# custom_numpad.net
KiCad netlist of a schematic drawn in EasyEDA
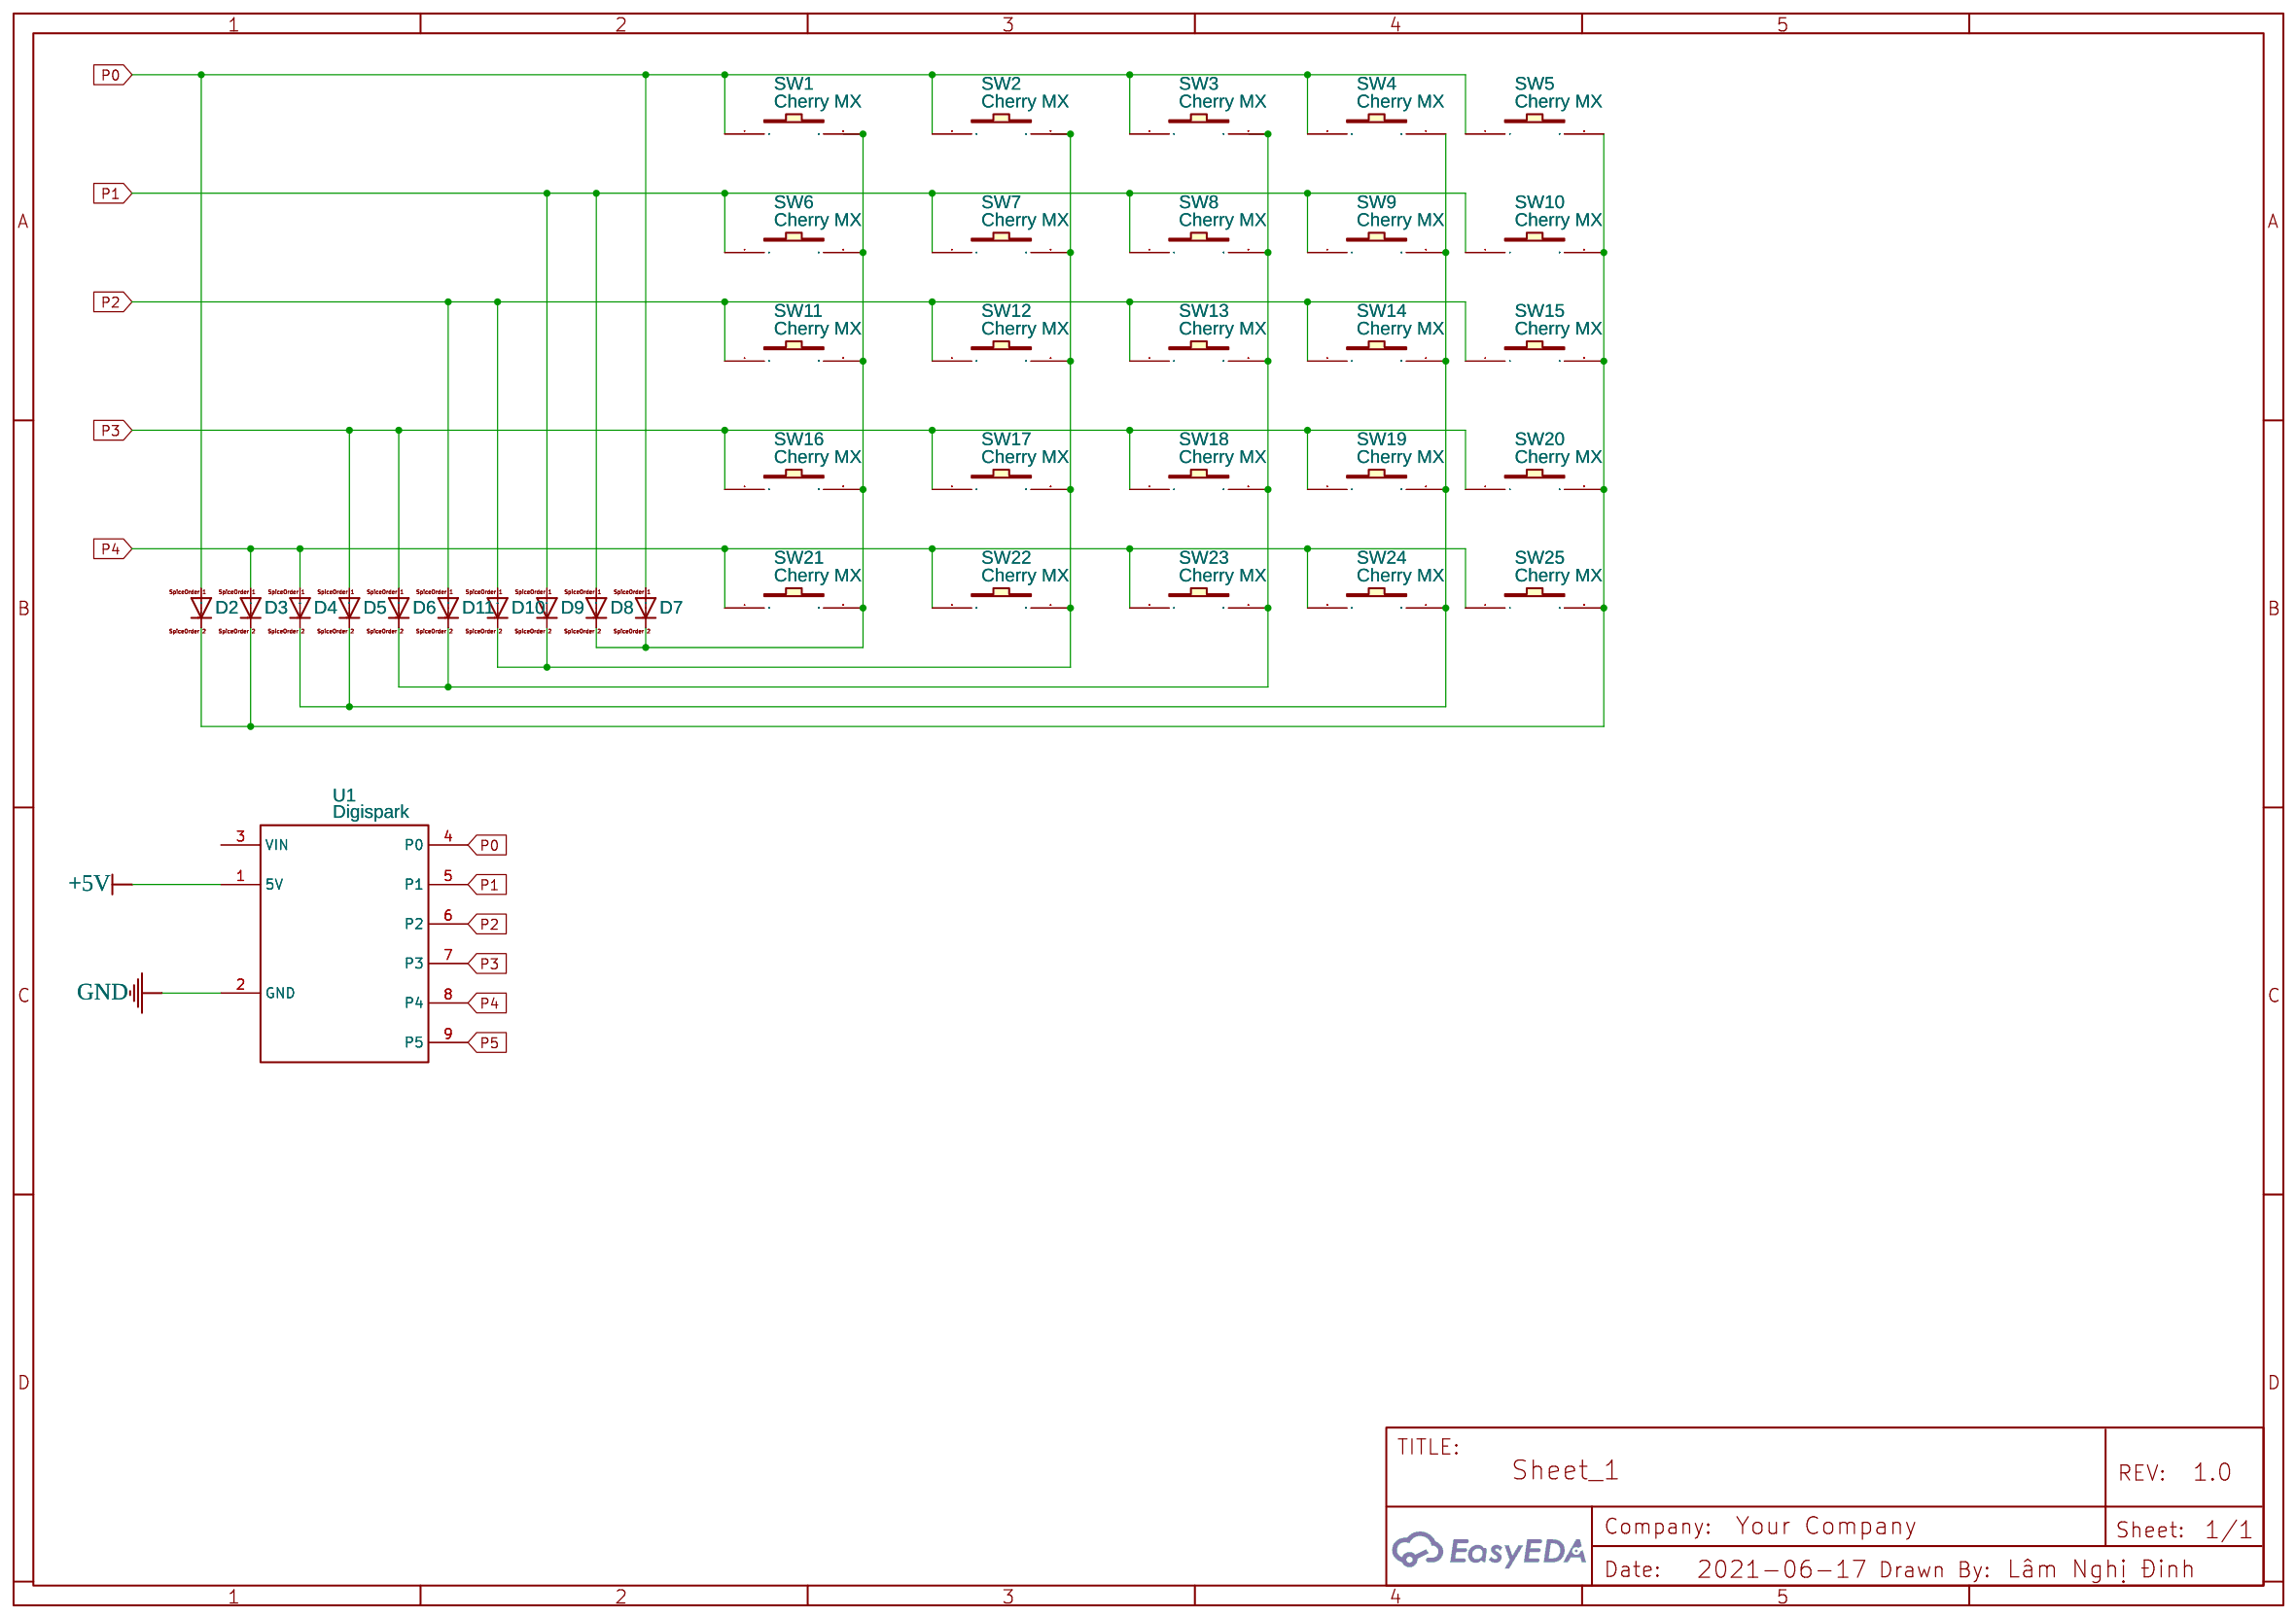
[diagram p0: schematic sheet]

(export (version "E")
  (design (tool "Eeschema 10.0.6"))
  (components
    (comp (ref "D2") (value "1N4148DO35-7") (libsource (lib "") (part "1N4148DO35-7")))
    (comp (ref "D3") (value "1N4148DO35-7") (libsource (lib "") (part "1N4148DO35-7")))
    (comp (ref "D4") (value "1N4148DO35-7") (libsource (lib "") (part "1N4148DO35-7")))
    (comp (ref "D5") (value "1N4148DO35-7") (libsource (lib "") (part "1N4148DO35-7")))
    (comp (ref "D6") (value "1N4148DO35-7") (libsource (lib "") (part "1N4148DO35-7")))
    (comp (ref "D7") (value "1N4148DO35-7") (libsource (lib "") (part "1N4148DO35-7")))
    (comp (ref "D8") (value "1N4148DO35-7") (libsource (lib "") (part "1N4148DO35-7")))
    (comp (ref "D9") (value "1N4148DO35-7") (libsource (lib "") (part "1N4148DO35-7")))
    (comp (ref "D10") (value "1N4148DO35-7") (libsource (lib "") (part "1N4148DO35-7")))
    (comp (ref "D11") (value "1N4148DO35-7") (libsource (lib "") (part "1N4148DO35-7")))
    (comp (ref "SW1") (value "Cherry MX") (libsource (lib "") (part "Cherry MX")))
    (comp (ref "SW2") (value "Cherry MX") (libsource (lib "") (part "Cherry MX")))
    (comp (ref "SW3") (value "Cherry MX") (libsource (lib "") (part "Cherry MX")))
    (comp (ref "SW4") (value "Cherry MX") (libsource (lib "") (part "Cherry MX")))
    (comp (ref "SW5") (value "Cherry MX") (libsource (lib "") (part "Cherry MX")))
    (comp (ref "SW6") (value "Cherry MX") (libsource (lib "") (part "Cherry MX")))
    (comp (ref "SW7") (value "Cherry MX") (libsource (lib "") (part "Cherry MX")))
    (comp (ref "SW8") (value "Cherry MX") (libsource (lib "") (part "Cherry MX")))
    (comp (ref "SW9") (value "Cherry MX") (libsource (lib "") (part "Cherry MX")))
    (comp (ref "SW10") (value "Cherry MX") (libsource (lib "") (part "Cherry MX")))
    (comp (ref "SW11") (value "Cherry MX") (libsource (lib "") (part "Cherry MX")))
    (comp (ref "SW12") (value "Cherry MX") (libsource (lib "") (part "Cherry MX")))
    (comp (ref "SW13") (value "Cherry MX") (libsource (lib "") (part "Cherry MX")))
    (comp (ref "SW14") (value "Cherry MX") (libsource (lib "") (part "Cherry MX")))
    (comp (ref "SW15") (value "Cherry MX") (libsource (lib "") (part "Cherry MX")))
    (comp (ref "SW16") (value "Cherry MX") (libsource (lib "") (part "Cherry MX")))
    (comp (ref "SW17") (value "Cherry MX") (libsource (lib "") (part "Cherry MX")))
    (comp (ref "SW18") (value "Cherry MX") (libsource (lib "") (part "Cherry MX")))
    (comp (ref "SW19") (value "Cherry MX") (libsource (lib "") (part "Cherry MX")))
    (comp (ref "SW20") (value "Cherry MX") (libsource (lib "") (part "Cherry MX")))
    (comp (ref "SW21") (value "Cherry MX") (libsource (lib "") (part "Cherry MX")))
    (comp (ref "SW22") (value "Cherry MX") (libsource (lib "") (part "Cherry MX")))
    (comp (ref "SW23") (value "Cherry MX") (libsource (lib "") (part "Cherry MX")))
    (comp (ref "SW24") (value "Cherry MX") (libsource (lib "") (part "Cherry MX")))
    (comp (ref "SW25") (value "Cherry MX") (libsource (lib "") (part "Cherry MX")))
    (comp (ref "U1")
      (value "Digispark")
      (fields
        (field (name "BOM_Manufacturer Part") "IMP1117AD33/T")
        (field (name "BOM_Supplier Part") "C72865")
      )
      (libsource (lib "") (part "Digispark"))
    )
  )
  (nets
    (net (code "1") (name "+5V") (class "Default")
      (node (ref "U1") (pin "1") (pinfunction "5V_1") (pintype "unspecified"))
    )
    (net (code "2") (name "GND") (class "Default")
      (node (ref "U1") (pin "2") (pinfunction "GND_2") (pintype "unspecified"))
    )
    (net (code "3") (name "Net-(D2-PadC)") (class "Default")
      (node (ref "D2") (pin "C") (pinfunction "C_C") (pintype "unspecified"))
      (node (ref "D3") (pin "C") (pinfunction "C_C") (pintype "unspecified"))
      (node (ref "SW10") (pin "2") (pinfunction "2_2") (pintype "input"))
      (node (ref "SW15") (pin "2") (pinfunction "2_2") (pintype "input"))
      (node (ref "SW20") (pin "2") (pinfunction "2_2") (pintype "input"))
      (node (ref "SW25") (pin "2") (pinfunction "2_2") (pintype "input"))
      (node (ref "SW5") (pin "2") (pinfunction "2_2") (pintype "input"))
    )
    (net (code "4") (name "Net-(D4-PadC)") (class "Default")
      (node (ref "D4") (pin "C") (pinfunction "C_C") (pintype "unspecified"))
      (node (ref "D5") (pin "C") (pinfunction "C_C") (pintype "unspecified"))
      (node (ref "SW14") (pin "2") (pinfunction "2_2") (pintype "input"))
      (node (ref "SW19") (pin "2") (pinfunction "2_2") (pintype "input"))
      (node (ref "SW24") (pin "2") (pinfunction "2_2") (pintype "input"))
      (node (ref "SW4") (pin "2") (pinfunction "2_2") (pintype "input"))
      (node (ref "SW9") (pin "2") (pinfunction "2_2") (pintype "input"))
    )
    (net (code "5") (name "Net-(D7-PadC)") (class "Default")
      (node (ref "D7") (pin "C") (pinfunction "C_C") (pintype "unspecified"))
      (node (ref "D8") (pin "C") (pinfunction "C_C") (pintype "unspecified"))
      (node (ref "SW1") (pin "2") (pinfunction "2_2") (pintype "input"))
      (node (ref "SW11") (pin "2") (pinfunction "2_2") (pintype "input"))
      (node (ref "SW16") (pin "2") (pinfunction "2_2") (pintype "input"))
      (node (ref "SW21") (pin "2") (pinfunction "2_2") (pintype "input"))
      (node (ref "SW6") (pin "2") (pinfunction "2_2") (pintype "input"))
    )
    (net (code "6") (name "Net-(D10-PadC)") (class "Default")
      (node (ref "D10") (pin "C") (pinfunction "C_C") (pintype "unspecified"))
      (node (ref "D9") (pin "C") (pinfunction "C_C") (pintype "unspecified"))
      (node (ref "SW12") (pin "2") (pinfunction "2_2") (pintype "input"))
      (node (ref "SW17") (pin "2") (pinfunction "2_2") (pintype "input"))
      (node (ref "SW2") (pin "2") (pinfunction "2_2") (pintype "input"))
      (node (ref "SW22") (pin "2") (pinfunction "2_2") (pintype "input"))
      (node (ref "SW7") (pin "2") (pinfunction "2_2") (pintype "input"))
    )
    (net (code "7") (name "Net-(D11-PadC)") (class "Default")
      (node (ref "D11") (pin "C") (pinfunction "C_C") (pintype "unspecified"))
      (node (ref "D6") (pin "C") (pinfunction "C_C") (pintype "unspecified"))
      (node (ref "SW13") (pin "2") (pinfunction "2_2") (pintype "input"))
      (node (ref "SW18") (pin "2") (pinfunction "2_2") (pintype "input"))
      (node (ref "SW23") (pin "2") (pinfunction "2_2") (pintype "input"))
      (node (ref "SW3") (pin "2") (pinfunction "2_2") (pintype "input"))
      (node (ref "SW8") (pin "2") (pinfunction "2_2") (pintype "input"))
    )
    (net (code "8") (name "P0") (class "Default")
      (node (ref "D2") (pin "A") (pinfunction "A_A") (pintype "unspecified"))
      (node (ref "D7") (pin "A") (pinfunction "A_A") (pintype "unspecified"))
      (node (ref "SW1") (pin "1") (pinfunction "1_1") (pintype "input"))
      (node (ref "SW2") (pin "1") (pinfunction "1_1") (pintype "input"))
      (node (ref "SW3") (pin "1") (pinfunction "1_1") (pintype "input"))
      (node (ref "SW4") (pin "1") (pinfunction "1_1") (pintype "input"))
      (node (ref "SW5") (pin "1") (pinfunction "1_1") (pintype "input"))
      (node (ref "U1") (pin "4") (pinfunction "P0_4") (pintype "unspecified"))
    )
    (net (code "9") (name "P1") (class "Default")
      (node (ref "D8") (pin "A") (pinfunction "A_A") (pintype "unspecified"))
      (node (ref "D9") (pin "A") (pinfunction "A_A") (pintype "unspecified"))
      (node (ref "SW10") (pin "1") (pinfunction "1_1") (pintype "input"))
      (node (ref "SW6") (pin "1") (pinfunction "1_1") (pintype "input"))
      (node (ref "SW7") (pin "1") (pinfunction "1_1") (pintype "input"))
      (node (ref "SW8") (pin "1") (pinfunction "1_1") (pintype "input"))
      (node (ref "SW9") (pin "1") (pinfunction "1_1") (pintype "input"))
      (node (ref "U1") (pin "5") (pinfunction "P1_5") (pintype "unspecified"))
    )
    (net (code "10") (name "P2") (class "Default")
      (node (ref "D10") (pin "A") (pinfunction "A_A") (pintype "unspecified"))
      (node (ref "D11") (pin "A") (pinfunction "A_A") (pintype "unspecified"))
      (node (ref "SW11") (pin "1") (pinfunction "1_1") (pintype "input"))
      (node (ref "SW12") (pin "1") (pinfunction "1_1") (pintype "input"))
      (node (ref "SW13") (pin "1") (pinfunction "1_1") (pintype "input"))
      (node (ref "SW14") (pin "1") (pinfunction "1_1") (pintype "input"))
      (node (ref "SW15") (pin "1") (pinfunction "1_1") (pintype "input"))
      (node (ref "U1") (pin "6") (pinfunction "P2_6") (pintype "unspecified"))
    )
    (net (code "11") (name "P3") (class "Default")
      (node (ref "D5") (pin "A") (pinfunction "A_A") (pintype "unspecified"))
      (node (ref "D6") (pin "A") (pinfunction "A_A") (pintype "unspecified"))
      (node (ref "SW16") (pin "1") (pinfunction "1_1") (pintype "input"))
      (node (ref "SW17") (pin "1") (pinfunction "1_1") (pintype "input"))
      (node (ref "SW18") (pin "1") (pinfunction "1_1") (pintype "input"))
      (node (ref "SW19") (pin "1") (pinfunction "1_1") (pintype "input"))
      (node (ref "SW20") (pin "1") (pinfunction "1_1") (pintype "input"))
      (node (ref "U1") (pin "7") (pinfunction "P3_7") (pintype "unspecified"))
    )
    (net (code "12") (name "P4") (class "Default")
      (node (ref "D3") (pin "A") (pinfunction "A_A") (pintype "unspecified"))
      (node (ref "D4") (pin "A") (pinfunction "A_A") (pintype "unspecified"))
      (node (ref "SW21") (pin "1") (pinfunction "1_1") (pintype "input"))
      (node (ref "SW22") (pin "1") (pinfunction "1_1") (pintype "input"))
      (node (ref "SW23") (pin "1") (pinfunction "1_1") (pintype "input"))
      (node (ref "SW24") (pin "1") (pinfunction "1_1") (pintype "input"))
      (node (ref "SW25") (pin "1") (pinfunction "1_1") (pintype "input"))
      (node (ref "U1") (pin "8") (pinfunction "P4_8") (pintype "unspecified"))
    )
    (net (code "13") (name "P5") (class "Default")
      (node (ref "U1") (pin "9") (pinfunction "P5_9") (pintype "unspecified"))
    )
    (net (code "14") (name "unconnected-(U1-VIN-Pad3)") (class "Default")
      (node (ref "U1") (pin "3") (pinfunction "VIN_3") (pintype "unspecified"))
    )
  )
)
